# Schematic_Day3.net
KiCad netlist of a schematic drawn in EAGLE
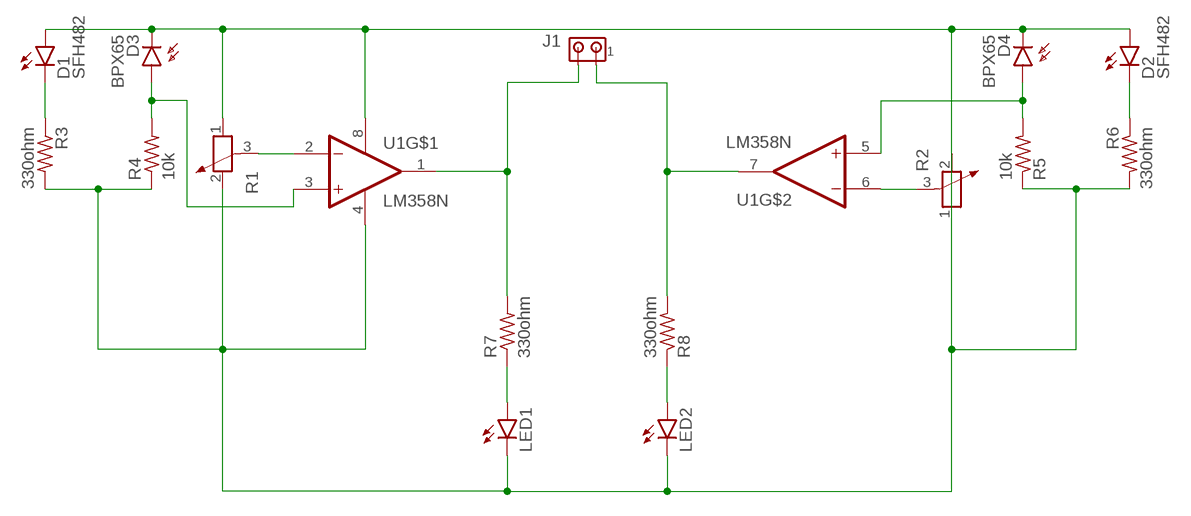
[diagram p0: schematic, sheet 1]

(export (version "E")
  (design (tool "Eeschema 10.0.6"))
  (components
    (comp (ref "D1")
      (value "SFH482")
      (footprint "eagle-import:SFH482")
      (libsource (lib "eagle-import") (part "SFH482"))
    )
    (comp (ref "D2")
      (value "SFH482")
      (footprint "eagle-import:SFH482")
      (libsource (lib "eagle-import") (part "SFH482"))
    )
    (comp (ref "D3")
      (value "BPX65")
      (footprint "eagle-import:BPX65")
      (fields (field (name "MPN") "BPX65."))
      (libsource (lib "eagle-import") (part "BPX65"))
    )
    (comp (ref "D4")
      (value "BPX65")
      (footprint "eagle-import:BPX65")
      (fields (field (name "MPN") "BPX65."))
      (libsource (lib "eagle-import") (part "BPX65"))
    )
    (comp (ref "J1")
      (value "MTA02-100")
      (footprint "eagle-import:10X02MTA")
      (libsource (lib "eagle-import") (part "MTA02-100"))
    )
    (comp (ref "LED1")
      (value "LED3MM")
      (footprint "eagle-import:LED3MM")
      (libsource (lib "eagle-import") (part "LED3MM"))
    )
    (comp (ref "LED2")
      (value "LED3MM")
      (footprint "eagle-import:LED3MM")
      (libsource (lib "eagle-import") (part "LED3MM"))
    )
    (comp (ref "R1")
      (value "POTENTIOMETER_PT-10")
      (footprint "eagle-import:PT-10")
      (libsource (lib "eagle-import") (part "POTENTIOMETER_PT-10"))
    )
    (comp (ref "R2")
      (value "POTENTIOMETER_PT-10")
      (footprint "eagle-import:PT-10")
      (libsource (lib "eagle-import") (part "POTENTIOMETER_PT-10"))
    )
    (comp (ref "R3")
      (value "330ohm")
      (footprint "eagle-import:0204_5")
      (libsource (lib "eagle-import") (part "R-US_0204/5"))
    )
    (comp (ref "R4")
      (value "10k")
      (footprint "eagle-import:0204_5")
      (libsource (lib "eagle-import") (part "R-US_0204/5"))
    )
    (comp (ref "R5")
      (value "10k")
      (footprint "eagle-import:0204_5")
      (libsource (lib "eagle-import") (part "R-US_0204/5"))
    )
    (comp (ref "R6")
      (value "330ohm")
      (footprint "eagle-import:0204_5")
      (libsource (lib "eagle-import") (part "R-US_0204/5"))
    )
    (comp (ref "R7")
      (value "330ohm")
      (footprint "eagle-import:0204_5")
      (libsource (lib "eagle-import") (part "R-US_0204/5"))
    )
    (comp (ref "R8")
      (value "330ohm")
      (footprint "eagle-import:0204_5")
      (libsource (lib "eagle-import") (part "R-US_0204/5"))
    )
    (comp (ref "U1")
      (value "LM358N")
      (footprint "eagle-import:DIP762W46P254L960H508Q8")
      (fields (field (name "MF") "Harris Corporation"))
      (libsource (lib "eagle-import") (part "LM358N"))
    )
  )
  (nets
    (net (code "1") (name "Net-(D1-C)") (class "Default")
      (node (ref "D1") (pin "K") (pinfunction "C_K") (pintype "passive"))
      (node (ref "R3") (pin "1") (pinfunction "1_1") (pintype "passive"))
    )
    (net (code "2") (name "Net-(D2-C)") (class "Default")
      (node (ref "D2") (pin "K") (pinfunction "C_K") (pintype "passive"))
      (node (ref "R6") (pin "1") (pinfunction "1_1") (pintype "passive"))
    )
    (net (code "3") (name "Net-(D3-C)") (class "Default")
      (node (ref "D1") (pin "A") (pinfunction "A_A") (pintype "passive"))
      (node (ref "D2") (pin "A") (pinfunction "A_A") (pintype "passive"))
      (node (ref "D3") (pin "K") (pinfunction "C_K") (pintype "passive"))
      (node (ref "D4") (pin "K") (pinfunction "C_K") (pintype "passive"))
      (node (ref "R1") (pin "1") (pinfunction "1_1") (pintype "passive"))
      (node (ref "R2") (pin "1") (pinfunction "1_1") (pintype "passive"))
      (node (ref "U1") (pin "8") (pinfunction "VCC_8") (pintype "power_in"))
    )
    (net (code "4") (name "Net-(LED1-C)") (class "Default")
      (node (ref "LED1") (pin "K") (pinfunction "C_K") (pintype "passive"))
      (node (ref "LED2") (pin "K") (pinfunction "C_K") (pintype "passive"))
      (node (ref "R1") (pin "2") (pinfunction "2_2") (pintype "passive"))
      (node (ref "R2") (pin "2") (pinfunction "2_2") (pintype "passive"))
      (node (ref "R3") (pin "2") (pinfunction "2_2") (pintype "passive"))
      (node (ref "R4") (pin "1") (pinfunction "1_1") (pintype "passive"))
      (node (ref "R5") (pin "1") (pinfunction "1_1") (pintype "passive"))
      (node (ref "R6") (pin "2") (pinfunction "2_2") (pintype "passive"))
      (node (ref "U1") (pin "4") (pinfunction "GND_4") (pintype "power_in"))
    )
    (net (code "5") (name "Net-(LED1-PadA)") (class "Default")
      (node (ref "LED1") (pin "A") (pinfunction "A_A") (pintype "passive"))
      (node (ref "R7") (pin "1") (pinfunction "1_1") (pintype "passive"))
    )
    (net (code "6") (name "Net-(LED2-PadA)") (class "Default")
      (node (ref "LED2") (pin "A") (pinfunction "A_A") (pintype "passive"))
      (node (ref "R8") (pin "1") (pinfunction "1_1") (pintype "passive"))
    )
    (net (code "7") (name "Net-(U1A-1IN+)") (class "Default")
      (node (ref "D3") (pin "A") (pinfunction "A_A") (pintype "passive"))
      (node (ref "R4") (pin "2") (pinfunction "2_2") (pintype "passive"))
      (node (ref "U1") (pin "3") (pinfunction "1IN+_3") (pintype "input"))
    )
    (net (code "8") (name "Net-(U1A-1IN-)") (class "Default")
      (node (ref "R1") (pin "3") (pinfunction "3_3") (pintype "passive"))
      (node (ref "U1") (pin "2") (pinfunction "1IN-_2") (pintype "input"))
    )
    (net (code "9") (name "Net-(U1A-1OUT)") (class "Default")
      (node (ref "J1") (pin "2") (pinfunction "2_2") (pintype "passive"))
      (node (ref "R7") (pin "2") (pinfunction "2_2") (pintype "passive"))
      (node (ref "U1") (pin "1") (pinfunction "1OUT_1") (pintype "output"))
    )
    (net (code "10") (name "Net-(U1B-2IN+)") (class "Default")
      (node (ref "D4") (pin "A") (pinfunction "A_A") (pintype "passive"))
      (node (ref "R5") (pin "2") (pinfunction "2_2") (pintype "passive"))
      (node (ref "U1") (pin "5") (pinfunction "2IN+_5") (pintype "input"))
    )
    (net (code "11") (name "Net-(U1B-2IN-)") (class "Default")
      (node (ref "R2") (pin "3") (pinfunction "3_3") (pintype "passive"))
      (node (ref "U1") (pin "6") (pinfunction "2IN-_6") (pintype "input"))
    )
    (net (code "12") (name "Net-(U1B-2OUT)") (class "Default")
      (node (ref "J1") (pin "1") (pinfunction "1_1") (pintype "passive"))
      (node (ref "R8") (pin "2") (pinfunction "2_2") (pintype "passive"))
      (node (ref "U1") (pin "7") (pinfunction "2OUT_7") (pintype "output"))
    )
  )
)
